# DotLogger.net
KiCad netlist of a schematic drawn in EAGLE
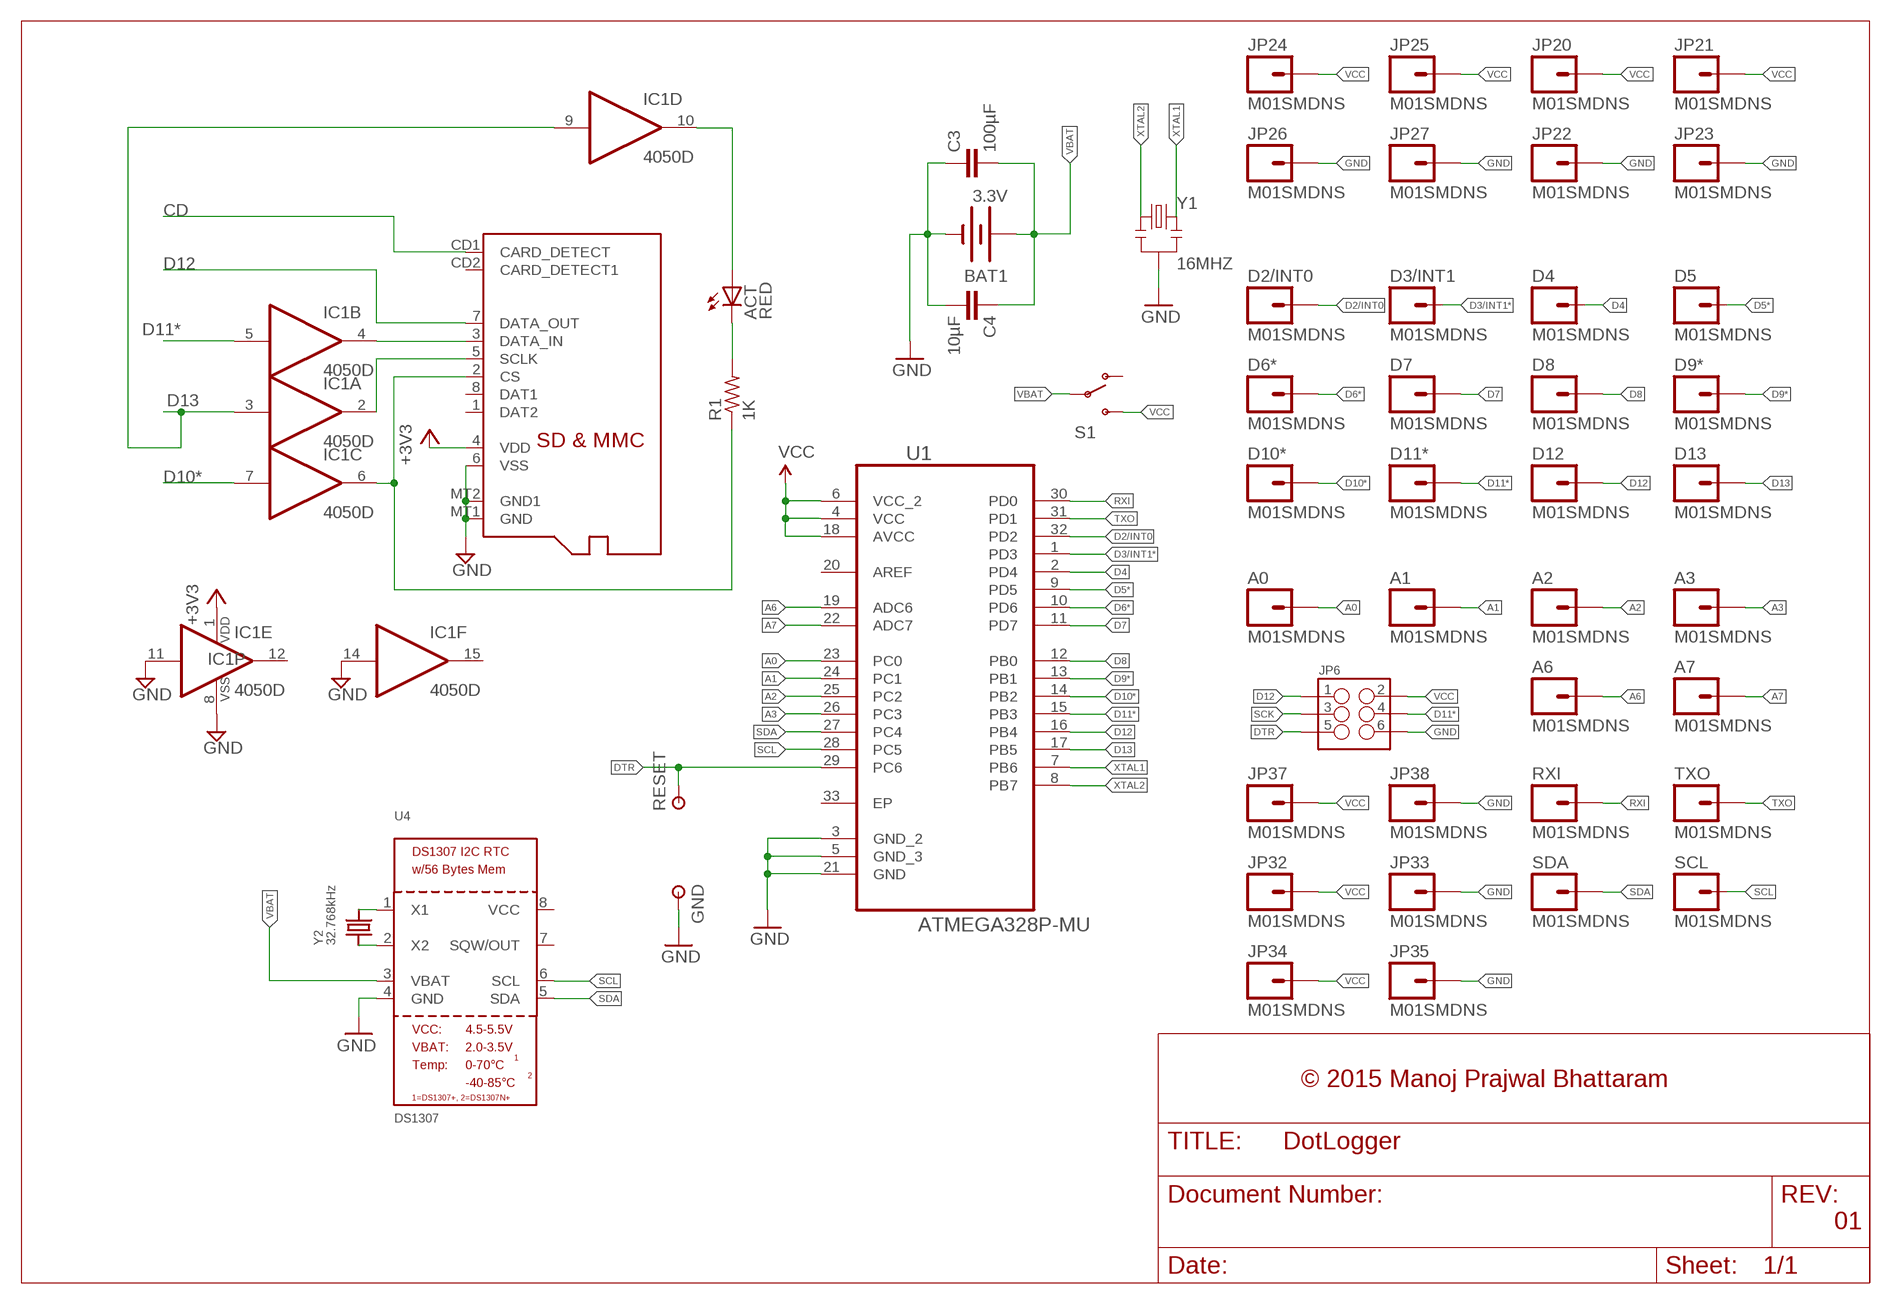
[diagram p0: schematic, sheet 1]

(export (version "E")
  (design (tool "Eeschema 10.0.6"))
  (components
    (comp (ref "A0")
      (value "M01SMDNS")
      (footprint "eagle-import:1X01NS")
      (libsource (lib "eagle-import") (part "M01SMDNS"))
    )
    (comp (ref "A1")
      (value "M01SMDNS")
      (footprint "eagle-import:1X01NS")
      (libsource (lib "eagle-import") (part "M01SMDNS"))
    )
    (comp (ref "A2")
      (value "M01SMDNS")
      (footprint "eagle-import:1X01NS")
      (libsource (lib "eagle-import") (part "M01SMDNS"))
    )
    (comp (ref "A3")
      (value "M01SMDNS")
      (footprint "eagle-import:1X01NS")
      (libsource (lib "eagle-import") (part "M01SMDNS"))
    )
    (comp (ref "A6")
      (value "M01SMDNS")
      (footprint "eagle-import:1X01NS")
      (libsource (lib "eagle-import") (part "M01SMDNS"))
    )
    (comp (ref "A7")
      (value "M01SMDNS")
      (footprint "eagle-import:1X01NS")
      (libsource (lib "eagle-import") (part "M01SMDNS"))
    )
    (comp (ref "ACT")
      (value "RED")
      (footprint "eagle-import:CHIP-LED0805")
      (libsource (lib "eagle-import") (part "LEDCHIP-LED0805"))
    )
    (comp (ref "BAT1")
      (value "3.3V")
      (footprint "eagle-import:BATTCON_20MM")
      (libsource (lib "eagle-import") (part "BATTERY20SMD"))
    )
    (comp (ref "C3")
      (value "100µF")
      (footprint "eagle-import:0402-CAP")
      (libsource (lib "eagle-import") (part "CAP0402-CAP"))
    )
    (comp (ref "C4")
      (value "10µF")
      (footprint "eagle-import:0402-CAP")
      (libsource (lib "eagle-import") (part "CAP0402-CAP"))
    )
    (comp (ref "D2/INT0")
      (value "M01SMDNS")
      (footprint "eagle-import:1X01NS")
      (libsource (lib "eagle-import") (part "M01SMDNS"))
    )
    (comp (ref "D3/INT1")
      (value "M01SMDNS")
      (footprint "eagle-import:1X01NS")
      (libsource (lib "eagle-import") (part "M01SMDNS"))
    )
    (comp (ref "D4")
      (value "M01SMDNS")
      (footprint "eagle-import:1X01NS")
      (libsource (lib "eagle-import") (part "M01SMDNS"))
    )
    (comp (ref "D5")
      (value "M01SMDNS")
      (footprint "eagle-import:1X01NS")
      (libsource (lib "eagle-import") (part "M01SMDNS"))
    )
    (comp (ref "D6*")
      (value "M01SMDNS")
      (footprint "eagle-import:1X01NS")
      (libsource (lib "eagle-import") (part "M01SMDNS"))
    )
    (comp (ref "D7")
      (value "M01SMDNS")
      (footprint "eagle-import:1X01NS")
      (libsource (lib "eagle-import") (part "M01SMDNS"))
    )
    (comp (ref "D8")
      (value "M01SMDNS")
      (footprint "eagle-import:1X01NS")
      (libsource (lib "eagle-import") (part "M01SMDNS"))
    )
    (comp (ref "D9*")
      (value "M01SMDNS")
      (footprint "eagle-import:1X01NS")
      (libsource (lib "eagle-import") (part "M01SMDNS"))
    )
    (comp (ref "D10*")
      (value "M01SMDNS")
      (footprint "eagle-import:1X01NS")
      (libsource (lib "eagle-import") (part "M01SMDNS"))
    )
    (comp (ref "D11*")
      (value "M01SMDNS")
      (footprint "eagle-import:1X01NS")
      (libsource (lib "eagle-import") (part "M01SMDNS"))
    )
    (comp (ref "D12")
      (value "M01SMDNS")
      (footprint "eagle-import:1X01NS")
      (libsource (lib "eagle-import") (part "M01SMDNS"))
    )
    (comp (ref "D13")
      (value "M01SMDNS")
      (footprint "eagle-import:1X01NS")
      (libsource (lib "eagle-import") (part "M01SMDNS"))
    )
    (comp (ref "GND")
      (value "PAD-TESTPOINT")
      (footprint "eagle-import:1,6_0,8")
      (libsource (lib "eagle-import") (part "PAD-TESTPOINT"))
    )
    (comp (ref "IC1")
      (value "4050D")
      (footprint "eagle-import:SO16")
      (libsource (lib "eagle-import") (part "4050D"))
    )
    (comp (ref "JP6")
      (value "M03X2POGO_PINS")
      (footprint "eagle-import:2X3_POGO")
      (libsource (lib "eagle-import") (part "M03X2POGO_PINS"))
    )
    (comp (ref "JP20")
      (value "M01SMDNS")
      (footprint "eagle-import:1X01NS")
      (libsource (lib "eagle-import") (part "M01SMDNS"))
    )
    (comp (ref "JP21")
      (value "M01SMDNS")
      (footprint "eagle-import:1X01NS")
      (libsource (lib "eagle-import") (part "M01SMDNS"))
    )
    (comp (ref "JP22")
      (value "M01SMDNS")
      (footprint "eagle-import:1X01NS")
      (libsource (lib "eagle-import") (part "M01SMDNS"))
    )
    (comp (ref "JP23")
      (value "M01SMDNS")
      (footprint "eagle-import:1X01NS")
      (libsource (lib "eagle-import") (part "M01SMDNS"))
    )
    (comp (ref "JP24")
      (value "M01SMDNS")
      (footprint "eagle-import:1X01NS")
      (libsource (lib "eagle-import") (part "M01SMDNS"))
    )
    (comp (ref "JP25")
      (value "M01SMDNS")
      (footprint "eagle-import:1X01NS")
      (libsource (lib "eagle-import") (part "M01SMDNS"))
    )
    (comp (ref "JP26")
      (value "M01SMDNS")
      (footprint "eagle-import:1X01NS")
      (libsource (lib "eagle-import") (part "M01SMDNS"))
    )
    (comp (ref "JP27")
      (value "M01SMDNS")
      (footprint "eagle-import:1X01NS")
      (libsource (lib "eagle-import") (part "M01SMDNS"))
    )
    (comp (ref "JP32")
      (value "M01SMDNS")
      (footprint "eagle-import:1X01NS")
      (libsource (lib "eagle-import") (part "M01SMDNS"))
    )
    (comp (ref "JP33")
      (value "M01SMDNS")
      (footprint "eagle-import:1X01NS")
      (libsource (lib "eagle-import") (part "M01SMDNS"))
    )
    (comp (ref "JP34")
      (value "M01SMDNS")
      (footprint "eagle-import:1X01NS")
      (libsource (lib "eagle-import") (part "M01SMDNS"))
    )
    (comp (ref "JP35")
      (value "M01SMDNS")
      (footprint "eagle-import:1X01NS")
      (libsource (lib "eagle-import") (part "M01SMDNS"))
    )
    (comp (ref "JP37")
      (value "M01SMDNS")
      (footprint "eagle-import:1X01NS")
      (libsource (lib "eagle-import") (part "M01SMDNS"))
    )
    (comp (ref "JP38")
      (value "M01SMDNS")
      (footprint "eagle-import:1X01NS")
      (libsource (lib "eagle-import") (part "M01SMDNS"))
    )
    (comp (ref "R1")
      (value "1K")
      (footprint "eagle-import:R0805")
      (libsource (lib "eagle-import") (part "R-US_R0805"))
    )
    (comp (ref "RESET")
      (value "PAD-TESTPOINT")
      (footprint "eagle-import:1,6_0,8")
      (libsource (lib "eagle-import") (part "PAD-TESTPOINT"))
    )
    (comp (ref "RXI")
      (value "M01SMDNS")
      (footprint "eagle-import:1X01NS")
      (libsource (lib "eagle-import") (part "M01SMDNS"))
    )
    (comp (ref "S1")
      (value "SWITCH-SPDT-SMD-A")
      (footprint "eagle-import:SWITCH-SPST-SMD-A")
      (libsource (lib "eagle-import") (part "SWITCH-SPDT-SMD-A"))
    )
    (comp (ref "SCL")
      (value "M01SMDNS")
      (footprint "eagle-import:1X01NS")
      (libsource (lib "eagle-import") (part "M01SMDNS"))
    )
    (comp (ref "SDA")
      (value "M01SMDNS")
      (footprint "eagle-import:1X01NS")
      (libsource (lib "eagle-import") (part "M01SMDNS"))
    )
    (comp (ref "TXO")
      (value "M01SMDNS")
      (footprint "eagle-import:1X01NS")
      (libsource (lib "eagle-import") (part "M01SMDNS"))
    )
    (comp (ref "U1")
      (value "ATMEGA328P-MU")
      (footprint "eagle-import:QFN50P500X500X100-33N")
      (libsource (lib "eagle-import") (part "ATMEGA328P-MU"))
    )
    (comp (ref "U4")
      (value "DS1307")
      (footprint "eagle-import:SOIC8_150MIL")
      (libsource (lib "eagle-import") (part "RTC_DS1307"))
    )
    (comp (ref "X1")
      (value "MICROSD")
      (footprint "eagle-import:MICROSD")
      (libsource (lib "eagle-import") (part "MICROSD"))
    )
    (comp (ref "Y1")
      (value "16MHZ")
      (footprint "eagle-import:RESONATOR-SMD")
      (libsource (lib "eagle-import") (part "RESONATOR16MHZ"))
    )
    (comp (ref "Y2")
      (value "32.768kHz")
      (footprint "eagle-import:CRYSTAL_8X3.8")
      (libsource (lib "eagle-import") (part "CRYSTAL8X3.8SMT"))
    )
  )
  (nets
    (net (code "1") (name "+3V3") (class "Default")
      (node (ref "IC1") (pin "1") (pinfunction "VDD_1") (pintype "power_in"))
      (node (ref "X1") (pin "4") (pinfunction "VDD_4") (pintype "power_in"))
    )
    (net (code "2") (name "/CD") (class "Default")
      (node (ref "X1") (pin "CD1") (pinfunction "CARD_DETECT_CD1") (pintype "passive"))
    )
    (net (code "3") (name "A0") (class "Default")
      (node (ref "A0") (pin "1") (pinfunction "1_1") (pintype "passive"))
      (node (ref "U1") (pin "23") (pinfunction "PC0_23") (pintype "bidirectional"))
    )
    (net (code "4") (name "A1") (class "Default")
      (node (ref "A1") (pin "1") (pinfunction "1_1") (pintype "passive"))
      (node (ref "U1") (pin "24") (pinfunction "PC1_24") (pintype "bidirectional"))
    )
    (net (code "5") (name "A2") (class "Default")
      (node (ref "A2") (pin "1") (pinfunction "1_1") (pintype "passive"))
      (node (ref "U1") (pin "25") (pinfunction "PC2_25") (pintype "bidirectional"))
    )
    (net (code "6") (name "A3") (class "Default")
      (node (ref "A3") (pin "1") (pinfunction "1_1") (pintype "passive"))
      (node (ref "U1") (pin "26") (pinfunction "PC3_26") (pintype "bidirectional"))
    )
    (net (code "7") (name "A6") (class "Default")
      (node (ref "A6") (pin "1") (pinfunction "1_1") (pintype "passive"))
      (node (ref "U1") (pin "19") (pinfunction "ADC6_19") (pintype "input"))
    )
    (net (code "8") (name "A7") (class "Default")
      (node (ref "A7") (pin "1") (pinfunction "1_1") (pintype "passive"))
      (node (ref "U1") (pin "22") (pinfunction "ADC7_22") (pintype "input"))
    )
    (net (code "9") (name "D2{slash}INT0") (class "Default")
      (node (ref "D2/INT0") (pin "1") (pinfunction "1_1") (pintype "passive"))
      (node (ref "U1") (pin "32") (pinfunction "PD2_32") (pintype "bidirectional"))
    )
    (net (code "10") (name "D3{slash}INT1*") (class "Default")
      (node (ref "D3/INT1") (pin "1") (pinfunction "1_1") (pintype "passive"))
      (node (ref "U1") (pin "1") (pinfunction "PD3_1") (pintype "bidirectional"))
    )
    (net (code "11") (name "D4") (class "Default")
      (node (ref "D4") (pin "1") (pinfunction "1_1") (pintype "passive"))
      (node (ref "U1") (pin "2") (pinfunction "PD4_2") (pintype "bidirectional"))
    )
    (net (code "12") (name "D5*") (class "Default")
      (node (ref "D5") (pin "1") (pinfunction "1_1") (pintype "passive"))
      (node (ref "U1") (pin "9") (pinfunction "PD5_9") (pintype "bidirectional"))
    )
    (net (code "13") (name "D6*") (class "Default")
      (node (ref "D6*") (pin "1") (pinfunction "1_1") (pintype "passive"))
      (node (ref "U1") (pin "10") (pinfunction "PD6_10") (pintype "bidirectional"))
    )
    (net (code "14") (name "D7") (class "Default")
      (node (ref "D7") (pin "1") (pinfunction "1_1") (pintype "passive"))
      (node (ref "U1") (pin "11") (pinfunction "PD7_11") (pintype "bidirectional"))
    )
    (net (code "15") (name "D8") (class "Default")
      (node (ref "D8") (pin "1") (pinfunction "1_1") (pintype "passive"))
      (node (ref "U1") (pin "12") (pinfunction "PB0_12") (pintype "bidirectional"))
    )
    (net (code "16") (name "D9*") (class "Default")
      (node (ref "D9*") (pin "1") (pinfunction "1_1") (pintype "passive"))
      (node (ref "U1") (pin "13") (pinfunction "PB1_13") (pintype "bidirectional"))
    )
    (net (code "17") (name "D10*") (class "Default")
      (node (ref "D10*") (pin "1") (pinfunction "1_1") (pintype "passive"))
      (node (ref "IC1") (pin "7") (pinfunction "I_7") (pintype "input"))
      (node (ref "U1") (pin "14") (pinfunction "PB2_14") (pintype "bidirectional"))
    )
    (net (code "18") (name "D11*") (class "Default")
      (node (ref "D11*") (pin "1") (pinfunction "1_1") (pintype "passive"))
      (node (ref "IC1") (pin "5") (pinfunction "I_5") (pintype "input"))
      (node (ref "JP6") (pin "P$4") (pinfunction "4_P$4") (pintype "bidirectional"))
      (node (ref "U1") (pin "15") (pinfunction "PB3_15") (pintype "bidirectional"))
    )
    (net (code "19") (name "D12") (class "Default")
      (node (ref "D12") (pin "1") (pinfunction "1_1") (pintype "passive"))
      (node (ref "JP6") (pin "P$1") (pinfunction "1_P$1") (pintype "bidirectional"))
      (node (ref "U1") (pin "16") (pinfunction "PB4_16") (pintype "bidirectional"))
      (node (ref "X1") (pin "7") (pinfunction "DATA_OUT_7") (pintype "output"))
    )
    (net (code "20") (name "D13") (class "Default")
      (node (ref "D13") (pin "1") (pinfunction "1_1") (pintype "passive"))
      (node (ref "IC1") (pin "3") (pinfunction "I_3") (pintype "input"))
      (node (ref "IC1") (pin "9") (pinfunction "I_9") (pintype "input"))
      (node (ref "U1") (pin "17") (pinfunction "PB5_17") (pintype "bidirectional"))
    )
    (net (code "21") (name "DTR") (class "Default")
      (node (ref "JP6") (pin "P$5") (pinfunction "5_P$5") (pintype "bidirectional"))
      (node (ref "RESET") (pin "1") (pinfunction "P_1") (pintype "passive"))
      (node (ref "U1") (pin "29") (pinfunction "PC6_29") (pintype "bidirectional"))
    )
    (net (code "22") (name "GND") (class "Default")
      (node (ref "BAT1") (pin "2") (pinfunction "-_2") (pintype "power_in"))
      (node (ref "C3") (pin "1") (pinfunction "1_1") (pintype "passive"))
      (node (ref "C4") (pin "2") (pinfunction "2_2") (pintype "passive"))
      (node (ref "GND") (pin "1") (pinfunction "P_1") (pintype "passive"))
      (node (ref "IC1") (pin "11") (pinfunction "I_11") (pintype "input"))
      (node (ref "IC1") (pin "14") (pinfunction "I_14") (pintype "input"))
      (node (ref "IC1") (pin "8") (pinfunction "VSS_8") (pintype "power_in"))
      (node (ref "JP22") (pin "1") (pinfunction "1_1") (pintype "passive"))
      (node (ref "JP23") (pin "1") (pinfunction "1_1") (pintype "passive"))
      (node (ref "JP26") (pin "1") (pinfunction "1_1") (pintype "passive"))
      (node (ref "JP27") (pin "1") (pinfunction "1_1") (pintype "passive"))
      (node (ref "JP33") (pin "1") (pinfunction "1_1") (pintype "passive"))
      (node (ref "JP35") (pin "1") (pinfunction "1_1") (pintype "passive"))
      (node (ref "JP38") (pin "1") (pinfunction "1_1") (pintype "passive"))
      (node (ref "JP6") (pin "P$6") (pinfunction "6_P$6") (pintype "bidirectional"))
      (node (ref "U1") (pin "21") (pinfunction "GND_21") (pintype "passive"))
      (node (ref "U1") (pin "3") (pinfunction "GND_2_3") (pintype "passive"))
      (node (ref "U1") (pin "5") (pinfunction "GND_3_5") (pintype "passive"))
      (node (ref "U4") (pin "4") (pinfunction "GND_4") (pintype "bidirectional"))
      (node (ref "X1") (pin "6") (pinfunction "VSS_6") (pintype "power_in"))
      (node (ref "X1") (pin "MT1") (pinfunction "GND_MT1") (pintype "power_in"))
      (node (ref "X1") (pin "MT2") (pinfunction "GND1_MT2") (pintype "power_in"))
      (node (ref "Y1") (pin "2") (pinfunction "2_2") (pintype "passive"))
    )
    (net (code "23") (name "Net-(ACT-PadC)") (class "Default")
      (node (ref "ACT") (pin "C") (pinfunction "C_C") (pintype "passive"))
      (node (ref "R1") (pin "2") (pinfunction "2_2") (pintype "passive"))
    )
    (net (code "24") (name "Net-(IC1A-O)") (class "Default")
      (node (ref "IC1") (pin "2") (pinfunction "O_2") (pintype "output"))
      (node (ref "X1") (pin "5") (pinfunction "SCLK_5") (pintype "input"))
    )
    (net (code "25") (name "Net-(IC1B-O)") (class "Default")
      (node (ref "IC1") (pin "4") (pinfunction "O_4") (pintype "output"))
      (node (ref "X1") (pin "3") (pinfunction "DATA_IN_3") (pintype "input"))
    )
    (net (code "26") (name "Net-(IC1C-O)") (class "Default")
      (node (ref "IC1") (pin "6") (pinfunction "O_6") (pintype "output"))
      (node (ref "R1") (pin "1") (pinfunction "1_1") (pintype "passive"))
      (node (ref "X1") (pin "2") (pinfunction "CS_2") (pintype "input"))
    )
    (net (code "27") (name "Net-(IC1D-O)") (class "Default")
      (node (ref "ACT") (pin "A") (pinfunction "A_A") (pintype "passive"))
      (node (ref "IC1") (pin "10") (pinfunction "O_10") (pintype "output"))
    )
    (net (code "28") (name "Net-(U4-X1)") (class "Default")
      (node (ref "U4") (pin "1") (pinfunction "X1_1") (pintype "bidirectional"))
      (node (ref "Y2") (pin "P$4") (pinfunction "2_P$4") (pintype "passive"))
    )
    (net (code "29") (name "Net-(U4-X2)") (class "Default")
      (node (ref "U4") (pin "2") (pinfunction "X2_2") (pintype "bidirectional"))
      (node (ref "Y2") (pin "P$1") (pinfunction "1_P$1") (pintype "passive"))
    )
    (net (code "30") (name "RXI") (class "Default")
      (node (ref "RXI") (pin "1") (pinfunction "1_1") (pintype "passive"))
      (node (ref "U1") (pin "30") (pinfunction "PD0_30") (pintype "bidirectional"))
    )
    (net (code "31") (name "SCK") (class "Default")
      (node (ref "JP6") (pin "P$3") (pinfunction "3_P$3") (pintype "bidirectional"))
    )
    (net (code "32") (name "SCL") (class "Default")
      (node (ref "SCL") (pin "1") (pinfunction "1_1") (pintype "passive"))
      (node (ref "U1") (pin "28") (pinfunction "PC5_28") (pintype "bidirectional"))
      (node (ref "U4") (pin "6") (pinfunction "SCL_6") (pintype "bidirectional"))
    )
    (net (code "33") (name "SDA") (class "Default")
      (node (ref "SDA") (pin "1") (pinfunction "1_1") (pintype "passive"))
      (node (ref "U1") (pin "27") (pinfunction "PC4_27") (pintype "bidirectional"))
      (node (ref "U4") (pin "5") (pinfunction "SDA_5") (pintype "bidirectional"))
    )
    (net (code "34") (name "TXO") (class "Default")
      (node (ref "TXO") (pin "1") (pinfunction "1_1") (pintype "passive"))
      (node (ref "U1") (pin "31") (pinfunction "PD1_31") (pintype "bidirectional"))
    )
    (net (code "35") (name "VBAT") (class "Default")
      (node (ref "BAT1") (pin "1") (pinfunction "+_1") (pintype "power_in"))
      (node (ref "C3") (pin "2") (pinfunction "2_2") (pintype "passive"))
      (node (ref "C4") (pin "1") (pinfunction "1_1") (pintype "passive"))
      (node (ref "S1") (pin "2") (pinfunction "P_2") (pintype "passive"))
      (node (ref "U4") (pin "3") (pinfunction "VBAT_3") (pintype "bidirectional"))
    )
    (net (code "36") (name "VCC") (class "Default")
      (node (ref "JP20") (pin "1") (pinfunction "1_1") (pintype "passive"))
      (node (ref "JP21") (pin "1") (pinfunction "1_1") (pintype "passive"))
      (node (ref "JP24") (pin "1") (pinfunction "1_1") (pintype "passive"))
      (node (ref "JP25") (pin "1") (pinfunction "1_1") (pintype "passive"))
      (node (ref "JP32") (pin "1") (pinfunction "1_1") (pintype "passive"))
      (node (ref "JP34") (pin "1") (pinfunction "1_1") (pintype "passive"))
      (node (ref "JP37") (pin "1") (pinfunction "1_1") (pintype "passive"))
      (node (ref "JP6") (pin "P$2") (pinfunction "2_P$2") (pintype "bidirectional"))
      (node (ref "S1") (pin "3") (pinfunction "S_3") (pintype "passive"))
      (node (ref "U1") (pin "18") (pinfunction "AVCC_18") (pintype "power_in"))
      (node (ref "U1") (pin "4") (pinfunction "VCC_4") (pintype "power_in"))
      (node (ref "U1") (pin "6") (pinfunction "VCC_2_6") (pintype "power_in"))
    )
    (net (code "37") (name "XTAL1") (class "Default")
      (node (ref "U1") (pin "7") (pinfunction "PB6_7") (pintype "bidirectional"))
      (node (ref "Y1") (pin "3") (pinfunction "3_3") (pintype "passive"))
    )
    (net (code "38") (name "XTAL2") (class "Default")
      (node (ref "U1") (pin "8") (pinfunction "PB7_8") (pintype "bidirectional"))
      (node (ref "Y1") (pin "1") (pinfunction "1_1") (pintype "passive"))
    )
    (net (code "39") (name "unconnected-(IC1E-O-Pad12)") (class "Default")
      (node (ref "IC1") (pin "12") (pinfunction "O_12") (pintype "output"))
    )
    (net (code "40") (name "unconnected-(IC1F-O-Pad15)") (class "Default")
      (node (ref "IC1") (pin "15") (pinfunction "O_15") (pintype "output"))
    )
    (net (code "41") (name "unconnected-(S1-O-Pad1)") (class "Default")
      (node (ref "S1") (pin "1") (pinfunction "O_1") (pintype "passive"))
    )
    (net (code "42") (name "unconnected-(U1-AREF-Pad20)") (class "Default")
      (node (ref "U1") (pin "20") (pinfunction "AREF_20") (pintype "input"))
    )
    (net (code "43") (name "unconnected-(U1-EP-Pad33)") (class "Default")
      (node (ref "U1") (pin "33") (pinfunction "EP_33") (pintype "passive"))
    )
    (net (code "44") (name "unconnected-(U4-SQW{slash}OUT-Pad7)") (class "Default")
      (node (ref "U4") (pin "7") (pinfunction "SQW/OUT_7") (pintype "bidirectional"))
    )
    (net (code "45") (name "unconnected-(U4-VCC-Pad8)") (class "Default")
      (node (ref "U4") (pin "8") (pinfunction "VCC_8") (pintype "bidirectional"))
    )
    (net (code "46") (name "unconnected-(X1-CARD_DETECT1-PadCD2)") (class "Default")
      (node (ref "X1") (pin "CD2") (pinfunction "CARD_DETECT1_CD2") (pintype "passive"))
    )
    (net (code "47") (name "unconnected-(X1-DAT1-Pad8)") (class "Default")
      (node (ref "X1") (pin "8") (pinfunction "DAT1_8") (pintype "bidirectional"))
    )
    (net (code "48") (name "unconnected-(X1-DAT2-Pad1)") (class "Default")
      (node (ref "X1") (pin "1") (pinfunction "DAT2_1") (pintype "bidirectional"))
    )
  )
)
